# TestBoard.net
KiCad netlist of a schematic drawn in EAGLE
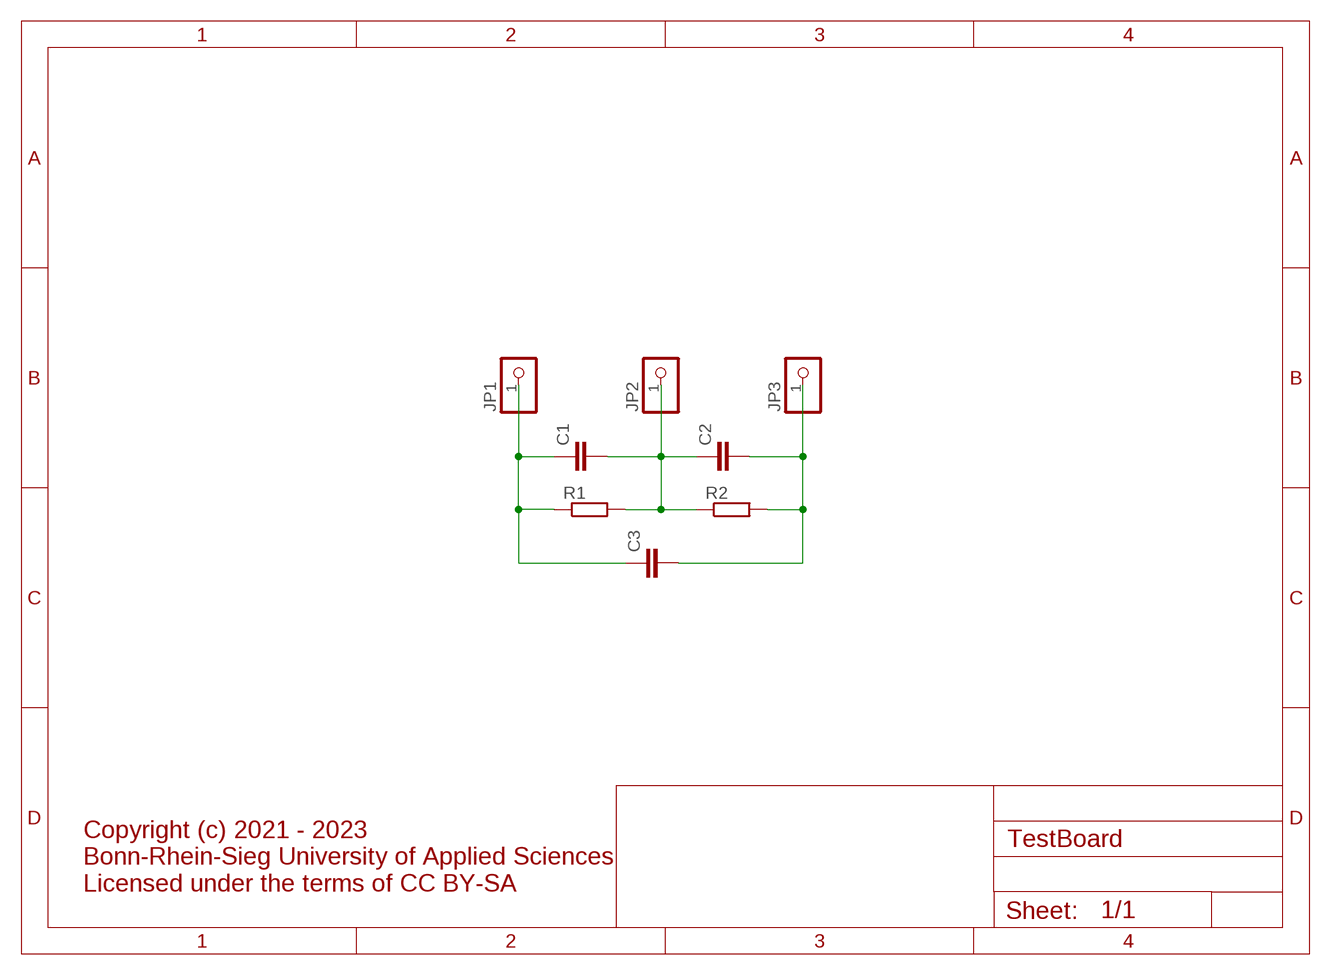
[diagram p0: schematic, sheet 1]

(export (version "E")
  (design (tool "Eeschema 10.0.6"))
  (components
    (comp (ref "C1")
      (value "C-EUC0603")
      (footprint "eagle-import:C0603")
      (libsource (lib "eagle-import") (part "C-EUC0603"))
    )
    (comp (ref "C2")
      (value "C-EUC0603")
      (footprint "eagle-import:C0603")
      (libsource (lib "eagle-import") (part "C-EUC0603"))
    )
    (comp (ref "C3")
      (value "C-EUC0603")
      (footprint "eagle-import:C0603")
      (libsource (lib "eagle-import") (part "C-EUC0603"))
    )
    (comp (ref "JP1")
      (value "PINHD-1X1")
      (footprint "eagle-import:1X01")
      (libsource (lib "eagle-import") (part "PINHD-1X1"))
    )
    (comp (ref "JP2")
      (value "PINHD-1X1")
      (footprint "eagle-import:1X01")
      (libsource (lib "eagle-import") (part "PINHD-1X1"))
    )
    (comp (ref "JP3")
      (value "PINHD-1X1")
      (footprint "eagle-import:1X01")
      (libsource (lib "eagle-import") (part "PINHD-1X1"))
    )
    (comp (ref "R1")
      (value "R-EU_R0603")
      (footprint "eagle-import:R0603")
      (libsource (lib "eagle-import") (part "R-EU_R0603"))
    )
    (comp (ref "R2")
      (value "R-EU_R0603")
      (footprint "eagle-import:R0603")
      (libsource (lib "eagle-import") (part "R-EU_R0603"))
    )
  )
  (nets
    (net (code "1") (name "Net-(C1-Pad1)") (class "Default")
      (node (ref "C1") (pin "1") (pinfunction "1_1") (pintype "passive"))
      (node (ref "C3") (pin "1") (pinfunction "1_1") (pintype "passive"))
      (node (ref "JP1") (pin "1") (pinfunction "1_1") (pintype "passive"))
      (node (ref "R1") (pin "1") (pinfunction "1_1") (pintype "passive"))
    )
    (net (code "2") (name "Net-(C1-Pad2)") (class "Default")
      (node (ref "C1") (pin "2") (pinfunction "2_2") (pintype "passive"))
      (node (ref "C2") (pin "1") (pinfunction "1_1") (pintype "passive"))
      (node (ref "JP2") (pin "1") (pinfunction "1_1") (pintype "passive"))
      (node (ref "R1") (pin "2") (pinfunction "2_2") (pintype "passive"))
      (node (ref "R2") (pin "1") (pinfunction "1_1") (pintype "passive"))
    )
    (net (code "3") (name "Net-(C2-Pad2)") (class "Default")
      (node (ref "C2") (pin "2") (pinfunction "2_2") (pintype "passive"))
      (node (ref "C3") (pin "2") (pinfunction "2_2") (pintype "passive"))
      (node (ref "JP3") (pin "1") (pinfunction "1_1") (pintype "passive"))
      (node (ref "R2") (pin "2") (pinfunction "2_2") (pintype "passive"))
    )
  )
)
